# SCH_Uno-Balancer.net
KiCad netlist of a schematic drawn in Altium Designer
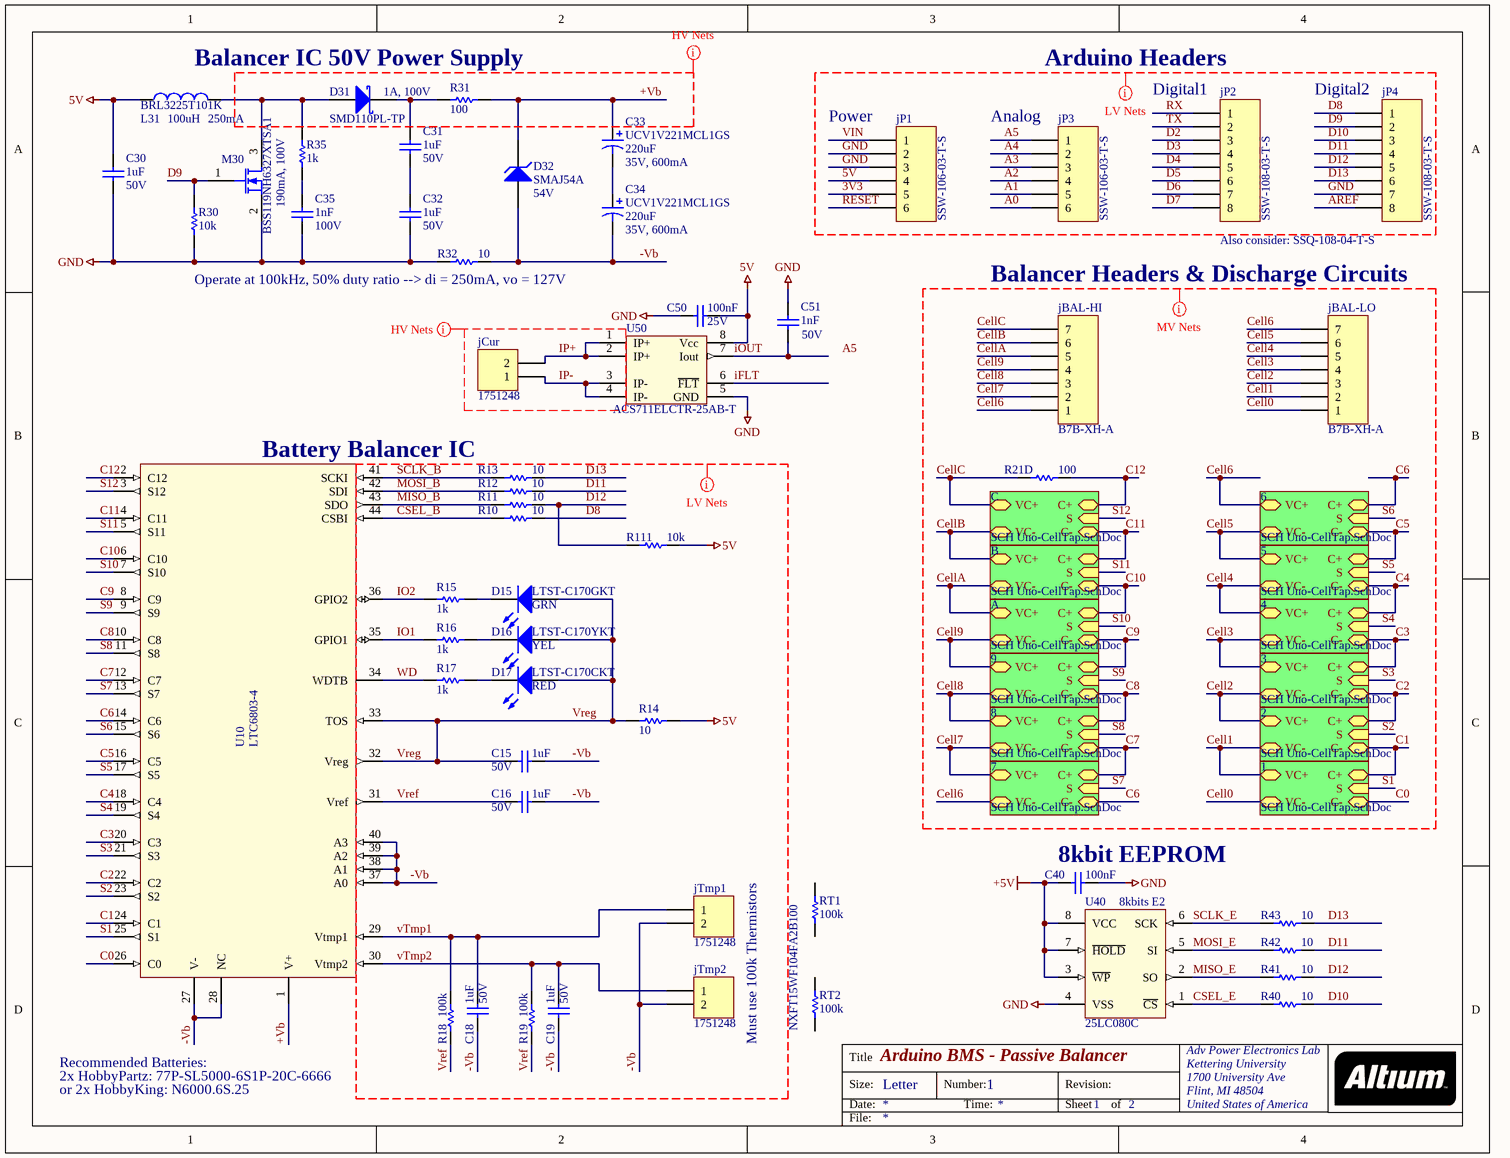
[diagram p0: SCH Uno-Balancer.SchDoc]

(export (version "E")
  (design (tool "Eeschema 10.0.6"))
  (components
    (comp (ref "C15")
      (value "1uF")
      (footprint "CAPC2012N")
      (description "Capacitor")
      (fields (field (name "RATED") "50V") (field (name "Comment") "CL21F105ZBFNNNE"))
      (libsource (lib "Miscellaneous Devices") (part "Cap"))
    )
    (comp (ref "C16")
      (value "1uF")
      (footprint "CAPC2012N")
      (description "Capacitor")
      (fields (field (name "RATED") "50V") (field (name "Comment") "CL21F105ZBFNNNE"))
      (libsource (lib "Miscellaneous Devices") (part "Cap"))
    )
    (comp (ref "C18")
      (value "1uF")
      (footprint "CAPC2012N")
      (description "Capacitor")
      (fields (field (name "RATED") "50V") (field (name "Comment") "CL21F105ZBFNNNE"))
      (libsource (lib "Miscellaneous Devices") (part "Cap"))
    )
    (comp (ref "C19")
      (value "1uF")
      (footprint "CAPC2012N")
      (description "Capacitor")
      (fields (field (name "RATED") "50V") (field (name "Comment") "CL21F105ZBFNNNE"))
      (libsource (lib "Miscellaneous Devices") (part "Cap"))
    )
    (comp (ref "C30")
      (value "1uF")
      (footprint "CAPC2012N")
      (description "Capacitor")
      (fields (field (name "RATED") "50V") (field (name "Comment") "CL21F105ZBFNNNE"))
      (libsource (lib "Miscellaneous Devices") (part "Cap"))
    )
    (comp (ref "C31")
      (value "1uF")
      (footprint "CAPC2012N")
      (description "Capacitor")
      (fields (field (name "RATED") "50V") (field (name "Comment") "CL21F105ZBFNNNE"))
      (libsource (lib "Miscellaneous Devices") (part "Cap"))
    )
    (comp (ref "C32")
      (value "1uF")
      (footprint "CAPC2012N")
      (description "Capacitor")
      (fields (field (name "RATED") "50V") (field (name "Comment") "CL21F105ZBFNNNE"))
      (libsource (lib "Miscellaneous Devices") (part "Cap"))
    )
    (comp (ref "C33")
      (value "UCV1V221MCL1GS")
      (footprint "CAP SMT 6.3x8mm")
      (description "Aluminum Electrolytic Capacitor")
      (fields (field (name "ALTIUM_VALUE") "220uF") (field (name "RATED") "35V, 600mA"))
      (libsource (lib "Miscellaneous Devices") (part "Cap Pol1"))
    )
    (comp (ref "C34")
      (value "UCV1V221MCL1GS")
      (footprint "CAP SMT 6.3x8mm")
      (description "Aluminum Electrolytic Capacitor")
      (fields (field (name "ALTIUM_VALUE") "220uF") (field (name "RATED") "35V, 600mA"))
      (libsource (lib "Miscellaneous Devices") (part "Cap Pol1"))
    )
    (comp (ref "C35")
      (value "1nF")
      (footprint "CAPC2012N")
      (description "Capacitor")
      (fields (field (name "RATED") "100V") (field (name "Comment") "C0805C102K1RACTU"))
      (libsource (lib "Miscellaneous Devices") (part "Cap"))
    )
    (comp (ref "C40")
      (value "100nF")
      (footprint "CAPC2012N")
      (description "Capacitor")
      (fields (field (name "Comment") "C0805C104Z5VACTU"))
      (libsource (lib "Miscellaneous Devices") (part "Cap"))
    )
    (comp (ref "C50")
      (value "100nF")
      (footprint "CAPC2012N")
      (description "Capacitor")
      (fields (field (name "RATED") "25V") (field (name "Comment") "C0805C104M3RACTU"))
      (libsource (lib "Miscellaneous Devices") (part "Cap"))
    )
    (comp (ref "C51")
      (value "1nF")
      (footprint "CAPC2012N")
      (description "Capacitor")
      (fields (field (name "RATED") "50V") (field (name "Comment") "C0805C102K5RACTU"))
      (libsource (lib "Miscellaneous Devices") (part "Cap"))
    )
    (comp (ref "D15")
      (value "LTST-C170GKT")
      (footprint "DIO2012N-G")
      (description "SMT Green Si LED")
      (fields (field (name "ALTIUM_VALUE") "GRN"))
      (libsource (lib "LIB SCH ArduinoBMS") (part "LTST-C170GKT"))
    )
    (comp (ref "D16")
      (value "LTST-C170YKT")
      (footprint "DIO2012N-Y")
      (description "SMT Yellow Si LED")
      (fields (field (name "ALTIUM_VALUE") "YEL"))
      (libsource (lib "LIB SCH ArduinoBMS") (part "LTST-C170YKT"))
    )
    (comp (ref "D17")
      (value "LTST-C170CKT")
      (footprint "DIO2012N-R")
      (description "SMT Red Si LED")
      (fields (field (name "ALTIUM_VALUE") "RED"))
      (libsource (lib "LIB SCH ArduinoBMS") (part "LTST-C170CKT"))
    )
    (comp (ref "D31")
      (value "SMD110PL-TP")
      (footprint "SOD123")
      (description "Silicon Schottky Diode, 1A, 100V")
      (fields (field (name "RATED") "1A, 100V"))
      (libsource (lib "LIB SCH ArduinoBMS") (part "SMD110PL-TP"))
    )
    (comp (ref "D32")
      (value "SMAJ54A")
      (footprint "DO214-SMA")
      (description "Zener Diode")
      (fields (field (name "ALTIUM_VALUE") "54V"))
      (libsource (lib "Miscellaneous Devices") (part "D Zener"))
    )
    (comp (ref "jBAL-HI")
      (value "B7B-XH-A")
      (footprint "JST-XH-B7")
      (description "JST Battery Balance Port Header, 7-Pin")
      (libsource (lib "LIB SCH ArduinoBMS") (part "JST B7B-XH-A"))
    )
    (comp (ref "jBAL-LO")
      (value "B7B-XH-A")
      (footprint "JST-XH-B7")
      (description "JST Battery Balance Port Header, 7-Pin")
      (libsource (lib "LIB SCH ArduinoBMS") (part "JST B7B-XH-A"))
    )
    (comp (ref "jCur")
      (value "1751248")
      (footprint "TERM2x3.5mm")
      (description "Header Conn Term Block, 2-Pin, 3.5mm Pitch")
      (libsource (lib "Miscellaneous Connectors") (part "Header 2"))
    )
    (comp (ref "jP1")
      (value "SSW-106-03-T-S")
      (footprint "HDR1X6")
      (description "Header, 6-Pin")
      (libsource (lib "Miscellaneous Connectors") (part "Header 6"))
    )
    (comp (ref "jP2")
      (value "SSW-108-03-T-S")
      (footprint "HDR1X8")
      (description "Header, 8-Pin")
      (libsource (lib "Miscellaneous Connectors") (part "Header 8"))
    )
    (comp (ref "jP3")
      (value "SSW-106-03-T-S")
      (footprint "HDR1X6")
      (description "Header, 6-Pin")
      (libsource (lib "Miscellaneous Connectors") (part "Header 6"))
    )
    (comp (ref "jP4")
      (value "SSW-108-03-T-S")
      (footprint "HDR1X8")
      (description "Header, 8-Pin")
      (libsource (lib "Miscellaneous Connectors") (part "Header 8"))
    )
    (comp (ref "jTmp1")
      (value "1751248")
      (footprint "TERM2x3.5mm")
      (description "Header Conn Term Block, 2-Pin, 3.5mm Pitch")
      (libsource (lib "") (part "Header 2_1"))
    )
    (comp (ref "jTmp2")
      (value "1751248")
      (footprint "TERM2x3.5mm")
      (description "Header Conn Term Block, 2-Pin, 3.5mm Pitch")
      (libsource (lib "") (part "Header 2_1"))
    )
    (comp (ref "L31")
      (value "BRL3225T101K")
      (footprint "INDC3225N")
      (description "Ferrite Bead Inductor")
      (fields (field (name "ALTIUM_VALUE") "100uH") (field (name "RATED") "250mA"))
      (libsource (lib "MagnaPFC") (part "BLM21P221SN"))
    )
    (comp (ref "M30")
      (value "BSS119NH6327XTSA1")
      (footprint "SOT23-3N")
      (description "Low-Power N-Channel MOSFET, 100V 170mA")
      (fields (field (name "RATED") "190mA, 100V"))
      (libsource (lib "LIB SCH ArduinoBMS") (part "BSS123"))
    )
    (comp (ref "R10")
      (value "10")
      (footprint "RESC2012N")
      (description "Resistor")
      (fields (field (name "Comment") "ERJ-6ENF10R0V"))
      (libsource (lib "Miscellaneous Devices") (part "Res1"))
    )
    (comp (ref "R11")
      (value "10")
      (footprint "RESC2012N")
      (description "Resistor")
      (fields (field (name "Comment") "ERJ-6ENF10R0V"))
      (libsource (lib "Miscellaneous Devices") (part "Res1"))
    )
    (comp (ref "R12")
      (value "10")
      (footprint "RESC2012N")
      (description "Resistor")
      (fields (field (name "Comment") "ERJ-6ENF10R0V"))
      (libsource (lib "Miscellaneous Devices") (part "Res1"))
    )
    (comp (ref "R13")
      (value "10")
      (footprint "RESC2012N")
      (description "Resistor")
      (fields (field (name "Comment") "ERJ-6ENF10R0V"))
      (libsource (lib "Miscellaneous Devices") (part "Res1"))
    )
    (comp (ref "R14")
      (value "10")
      (footprint "RESC2012N")
      (description "Resistor")
      (fields (field (name "Comment") "ERJ-6ENF10R0V"))
      (libsource (lib "Miscellaneous Devices") (part "Res1"))
    )
    (comp (ref "R15")
      (value "1k")
      (footprint "RESC2012N")
      (description "Resistor")
      (fields (field (name "Comment") "ERJ-6ENF1001V"))
      (libsource (lib "Miscellaneous Devices") (part "Res1"))
    )
    (comp (ref "R16")
      (value "1k")
      (footprint "RESC2012N")
      (description "Resistor")
      (fields (field (name "Comment") "ERJ-6ENF1001V"))
      (libsource (lib "Miscellaneous Devices") (part "Res1"))
    )
    (comp (ref "R17")
      (value "1k")
      (footprint "RESC2012N")
      (description "Resistor")
      (fields (field (name "Comment") "ERJ-6ENF1001V"))
      (libsource (lib "Miscellaneous Devices") (part "Res1"))
    )
    (comp (ref "R18")
      (value "100k")
      (footprint "RESC2012N")
      (description "Resistor")
      (fields (field (name "Comment") "ERJ-6ENF1003V"))
      (libsource (lib "Miscellaneous Devices") (part "Res1"))
    )
    (comp (ref "R19")
      (value "100k")
      (footprint "RESC2012N")
      (description "Resistor")
      (fields (field (name "Comment") "ERJ-6ENF1003V"))
      (libsource (lib "Miscellaneous Devices") (part "Res1"))
    )
    (comp (ref "R21D")
      (value "100")
      (footprint "RESC2012N")
      (description "Resistor")
      (fields (field (name "Comment") "ERJ-6ENF1000V"))
      (libsource (lib "Miscellaneous Devices") (part "Res1"))
    )
    (comp (ref "R30")
      (value "10k")
      (footprint "RESC2012N")
      (description "Resistor")
      (fields (field (name "Comment") "ERJ-6ENF1002V"))
      (libsource (lib "Miscellaneous Devices") (part "Res1"))
    )
    (comp (ref "R31")
      (value "100")
      (footprint "RESC2012N")
      (description "Resistor")
      (fields (field (name "Comment") "ERJ-6ENF1000V"))
      (libsource (lib "Miscellaneous Devices") (part "Res1"))
    )
    (comp (ref "R32")
      (value "10")
      (footprint "RESC2012N")
      (description "Resistor")
      (fields (field (name "Comment") "ERJ-6ENF10R0V"))
      (libsource (lib "Miscellaneous Devices") (part "Res1"))
    )
    (comp (ref "R35")
      (value "1k")
      (footprint "RESC2012N")
      (description "Resistor")
      (fields (field (name "Comment") "ERJ-6ENF1001V"))
      (libsource (lib "Miscellaneous Devices") (part "Res1"))
    )
    (comp (ref "R40")
      (value "10")
      (footprint "RESC2012N")
      (description "Resistor")
      (fields (field (name "Comment") "ERJ-6ENF10R0V"))
      (libsource (lib "Miscellaneous Devices") (part "Res1"))
    )
    (comp (ref "R41")
      (value "10")
      (footprint "RESC2012N")
      (description "Resistor")
      (fields (field (name "Comment") "ERJ-6ENF10R0V"))
      (libsource (lib "Miscellaneous Devices") (part "Res1"))
    )
    (comp (ref "R42")
      (value "10")
      (footprint "RESC2012N")
      (description "Resistor")
      (fields (field (name "Comment") "ERJ-6ENF10R0V"))
      (libsource (lib "Miscellaneous Devices") (part "Res1"))
    )
    (comp (ref "R43")
      (value "10")
      (footprint "RESC2012N")
      (description "Resistor")
      (fields (field (name "Comment") "ERJ-6ENF10R0V"))
      (libsource (lib "Miscellaneous Devices") (part "Res1"))
    )
    (comp (ref "R111")
      (value "10k")
      (footprint "RESC2012N")
      (description "Resistor")
      (fields (field (name "Comment") "ERJ-6ENF1002V"))
      (libsource (lib "Miscellaneous Devices") (part "Res1"))
    )
    (comp (ref "RT1")
      (value "100k")
      (description "NTC Thermistor Resistor")
      (fields (field (name "Comment") "NXFT15WF104FA2B100"))
      (libsource (lib "Miscellaneous Devices") (part "Res1"))
    )
    (comp (ref "RT2")
      (value "100k")
      (description "NTC Thermistor Resistor")
      (fields (field (name "Comment") "NXFT15WF104FA2B100"))
      (libsource (lib "Miscellaneous Devices") (part "Res1"))
    )
    (comp (ref "U10")
      (value "LTC6803-4")
      (footprint "SSOP44")
      (description "Multicell Battery Stack Monitor")
      (libsource (lib "LIB SCH Three Phase") (part "LTC6803-4"))
    )
    (comp (ref "U40")
      (value "25LC080C")
      (footprint "SOIC-8-150")
      (description "EEPROM 8kbit SPI Serial Interface")
      (fields (field (name "ALTIUM_VALUE") "8kbits E2"))
      (libsource (lib "LIB SCH NBT Inverter") (part "25LC080C"))
    )
    (comp (ref "U50")
      (value "ACS711ELCTR-25AB-T")
      (footprint "SOIC-8-150")
      (description "Internal Hall-Effect Current Transducer")
      (libsource (lib "LIB SCH NanoInv") (part "ACS711"))
    )
  )
  (nets
    (net (code "1") (name "+5V") (class "Default")
      (node (ref "C40") (pin "2") (pinfunction "2_2") (pintype "passive"))
      (node (ref "U40") (pin "3") (pinfunction "~{WP}_3") (pintype "input"))
      (node (ref "U40") (pin "7") (pinfunction "~{HOLD}_7") (pintype "input"))
      (node (ref "U40") (pin "8") (pinfunction "VCC_8") (pintype "power_in"))
    )
    (net (code "2") (name "/+Vb") (class "Default")
      (node (ref "C33") (pin "1") (pinfunction "1_1") (pintype "passive"))
      (node (ref "D32") (pin "2") (pinfunction "K_2") (pintype "passive"))
      (node (ref "R31") (pin "2") (pinfunction "2_2") (pintype "passive"))
      (node (ref "U10") (pin "1") (pinfunction "V+_1") (pintype "power_in"))
    )
    (net (code "3") (name "/-Vb") (class "Default")
      (node (ref "C15") (pin "1") (pinfunction "1_1") (pintype "passive"))
      (node (ref "C16") (pin "1") (pinfunction "1_1") (pintype "passive"))
      (node (ref "C18") (pin "1") (pinfunction "1_1") (pintype "passive"))
      (node (ref "C19") (pin "1") (pinfunction "1_1") (pintype "passive"))
      (node (ref "C34") (pin "2") (pinfunction "2_2") (pintype "passive"))
      (node (ref "D32") (pin "1") (pinfunction "A_1") (pintype "passive"))
      (node (ref "R32") (pin "2") (pinfunction "2_2") (pintype "passive"))
      (node (ref "U10") (pin "27") (pinfunction "V-_27") (pintype "power_in"))
      (node (ref "U10") (pin "28") (pinfunction "NC_28") (pintype "passive"))
      (node (ref "U10") (pin "37") (pinfunction "A0_37") (pintype "input"))
      (node (ref "U10") (pin "38") (pinfunction "A1_38") (pintype "input"))
      (node (ref "U10") (pin "39") (pinfunction "A2_39") (pintype "input"))
      (node (ref "U10") (pin "40") (pinfunction "A3_40") (pintype "input"))
      (node (ref "jTmp1") (pin "2") (pinfunction "2_2") (pintype "passive"))
      (node (ref "jTmp2") (pin "2") (pinfunction "2_2") (pintype "passive"))
    )
    (net (code "4") (name "/3V3") (class "Default")
      (node (ref "jP1") (pin "5") (pinfunction "5_5") (pintype "passive"))
    )
    (net (code "5") (name "/A0") (class "Default")
      (node (ref "jP3") (pin "6") (pinfunction "6_6") (pintype "passive"))
    )
    (net (code "6") (name "/A1") (class "Default")
      (node (ref "jP3") (pin "5") (pinfunction "5_5") (pintype "passive"))
    )
    (net (code "7") (name "/A2") (class "Default")
      (node (ref "jP3") (pin "4") (pinfunction "4_4") (pintype "passive"))
    )
    (net (code "8") (name "/A3") (class "Default")
      (node (ref "jP3") (pin "3") (pinfunction "3_3") (pintype "passive"))
    )
    (net (code "9") (name "/A4") (class "Default")
      (node (ref "jP3") (pin "2") (pinfunction "2_2") (pintype "passive"))
    )
    (net (code "10") (name "/A5") (class "Default")
      (node (ref "jP3") (pin "1") (pinfunction "1_1") (pintype "passive"))
    )
    (net (code "11") (name "/AREF") (class "Default")
      (node (ref "jP4") (pin "8") (pinfunction "8_8") (pintype "passive"))
    )
    (net (code "12") (name "/C0") (class "Default")
      (node (ref "U10") (pin "26") (pinfunction "C0_26") (pintype "input"))
    )
    (net (code "13") (name "/C1") (class "Default")
      (node (ref "U10") (pin "24") (pinfunction "C1_24") (pintype "input"))
    )
    (net (code "14") (name "/C2") (class "Default")
      (node (ref "U10") (pin "22") (pinfunction "C2_22") (pintype "input"))
    )
    (net (code "15") (name "/C3") (class "Default")
      (node (ref "U10") (pin "20") (pinfunction "C3_20") (pintype "input"))
    )
    (net (code "16") (name "/C4") (class "Default")
      (node (ref "U10") (pin "18") (pinfunction "C4_18") (pintype "input"))
    )
    (net (code "17") (name "/C5") (class "Default")
      (node (ref "U10") (pin "16") (pinfunction "C5_16") (pintype "input"))
    )
    (net (code "18") (name "/C6") (class "Default")
      (node (ref "U10") (pin "14") (pinfunction "C6_14") (pintype "input"))
    )
    (net (code "19") (name "/C7") (class "Default")
      (node (ref "U10") (pin "12") (pinfunction "C7_12") (pintype "input"))
    )
    (net (code "20") (name "/C8") (class "Default")
      (node (ref "U10") (pin "10") (pinfunction "C8_10") (pintype "input"))
    )
    (net (code "21") (name "/C9") (class "Default")
      (node (ref "U10") (pin "8") (pinfunction "C9_8") (pintype "input"))
    )
    (net (code "22") (name "/C10") (class "Default")
      (node (ref "U10") (pin "6") (pinfunction "C10_6") (pintype "input"))
    )
    (net (code "23") (name "/C11") (class "Default")
      (node (ref "U10") (pin "4") (pinfunction "C11_4") (pintype "input"))
    )
    (net (code "24") (name "/C12") (class "Default")
      (node (ref "R21D") (pin "2") (pinfunction "2_2") (pintype "passive"))
      (node (ref "U10") (pin "2") (pinfunction "C12_2") (pintype "input"))
    )
    (net (code "25") (name "/CSEL_B") (class "Default")
      (node (ref "R10") (pin "1") (pinfunction "1_1") (pintype "passive"))
      (node (ref "U10") (pin "44") (pinfunction "CSBI_44") (pintype "input"))
    )
    (net (code "26") (name "/CSEL_E") (class "Default")
      (node (ref "R40") (pin "1") (pinfunction "1_1") (pintype "passive"))
      (node (ref "U40") (pin "1") (pinfunction "~{CS}_1") (pintype "input"))
    )
    (net (code "27") (name "/Cell0") (class "Default")
      (node (ref "jBAL-LO") (pin "1") (pinfunction "1_1") (pintype "passive"))
    )
    (net (code "28") (name "/Cell1") (class "Default")
      (node (ref "jBAL-LO") (pin "2") (pinfunction "2_2") (pintype "passive"))
    )
    (net (code "29") (name "/Cell2") (class "Default")
      (node (ref "jBAL-LO") (pin "3") (pinfunction "3_3") (pintype "passive"))
    )
    (net (code "30") (name "/Cell3") (class "Default")
      (node (ref "jBAL-LO") (pin "4") (pinfunction "4_4") (pintype "passive"))
    )
    (net (code "31") (name "/Cell4") (class "Default")
      (node (ref "jBAL-LO") (pin "5") (pinfunction "5_5") (pintype "passive"))
    )
    (net (code "32") (name "/Cell5") (class "Default")
      (node (ref "jBAL-LO") (pin "6") (pinfunction "6_6") (pintype "passive"))
    )
    (net (code "33") (name "/Cell6") (class "Default")
      (node (ref "jBAL-HI") (pin "1") (pinfunction "1_1") (pintype "passive"))
      (node (ref "jBAL-LO") (pin "7") (pinfunction "7_7") (pintype "passive"))
    )
    (net (code "34") (name "/Cell7") (class "Default")
      (node (ref "jBAL-HI") (pin "2") (pinfunction "2_2") (pintype "passive"))
    )
    (net (code "35") (name "/Cell8") (class "Default")
      (node (ref "jBAL-HI") (pin "3") (pinfunction "3_3") (pintype "passive"))
    )
    (net (code "36") (name "/Cell9") (class "Default")
      (node (ref "jBAL-HI") (pin "4") (pinfunction "4_4") (pintype "passive"))
    )
    (net (code "37") (name "/CellA") (class "Default")
      (node (ref "jBAL-HI") (pin "5") (pinfunction "5_5") (pintype "passive"))
    )
    (net (code "38") (name "/CellB") (class "Default")
      (node (ref "jBAL-HI") (pin "6") (pinfunction "6_6") (pintype "passive"))
    )
    (net (code "39") (name "/CellC") (class "Default")
      (node (ref "R21D") (pin "1") (pinfunction "1_1") (pintype "passive"))
      (node (ref "jBAL-HI") (pin "7") (pinfunction "7_7") (pintype "passive"))
    )
    (net (code "40") (name "/D2") (class "Default")
      (node (ref "jP2") (pin "3") (pinfunction "3_3") (pintype "passive"))
    )
    (net (code "41") (name "/D3") (class "Default")
      (node (ref "jP2") (pin "4") (pinfunction "4_4") (pintype "passive"))
    )
    (net (code "42") (name "/D4") (class "Default")
      (node (ref "jP2") (pin "5") (pinfunction "5_5") (pintype "passive"))
    )
    (net (code "43") (name "/D5") (class "Default")
      (node (ref "jP2") (pin "6") (pinfunction "6_6") (pintype "passive"))
    )
    (net (code "44") (name "/D6") (class "Default")
      (node (ref "jP2") (pin "7") (pinfunction "7_7") (pintype "passive"))
    )
    (net (code "45") (name "/D7") (class "Default")
      (node (ref "jP2") (pin "8") (pinfunction "8_8") (pintype "passive"))
    )
    (net (code "46") (name "/D8") (class "Default")
      (node (ref "R10") (pin "2") (pinfunction "2_2") (pintype "passive"))
      (node (ref "jP4") (pin "1") (pinfunction "1_1") (pintype "passive"))
    )
    (net (code "47") (name "/D9") (class "Default")
      (node (ref "M30") (pin "1") (pinfunction "G_1") (pintype "passive"))
      (node (ref "R30") (pin "1") (pinfunction "1_1") (pintype "passive"))
      (node (ref "jP4") (pin "2") (pinfunction "2_2") (pintype "passive"))
    )
    (net (code "48") (name "/D10") (class "Default")
      (node (ref "R40") (pin "2") (pinfunction "2_2") (pintype "passive"))
      (node (ref "jP4") (pin "3") (pinfunction "3_3") (pintype "passive"))
    )
    (net (code "49") (name "/D11") (class "Default")
      (node (ref "R12") (pin "2") (pinfunction "2_2") (pintype "passive"))
      (node (ref "R42") (pin "2") (pinfunction "2_2") (pintype "passive"))
      (node (ref "jP4") (pin "4") (pinfunction "4_4") (pintype "passive"))
    )
    (net (code "50") (name "/D12") (class "Default")
      (node (ref "R11") (pin "2") (pinfunction "2_2") (pintype "passive"))
      (node (ref "R111") (pin "1") (pinfunction "1_1") (pintype "passive"))
      (node (ref "R41") (pin "2") (pinfunction "2_2") (pintype "passive"))
      (node (ref "jP4") (pin "5") (pinfunction "5_5") (pintype "passive"))
    )
    (net (code "51") (name "/D13") (class "Default")
      (node (ref "R13") (pin "2") (pinfunction "2_2") (pintype "passive"))
      (node (ref "R43") (pin "2") (pinfunction "2_2") (pintype "passive"))
      (node (ref "jP4") (pin "6") (pinfunction "6_6") (pintype "passive"))
    )
    (net (code "52") (name "/IO1") (class "Default")
      (node (ref "R16") (pin "2") (pinfunction "2_2") (pintype "passive"))
      (node (ref "U10") (pin "35") (pinfunction "GPIO1_35") (pintype "bidirectional"))
    )
    (net (code "53") (name "/IO2") (class "Default")
      (node (ref "R15") (pin "2") (pinfunction "2_2") (pintype "passive"))
      (node (ref "U10") (pin "36") (pinfunction "GPIO2_36") (pintype "bidirectional"))
    )
    (net (code "54") (name "/IP+") (class "Default")
      (node (ref "U50") (pin "1") (pinfunction "IP+_1") (pintype "passive"))
      (node (ref "U50") (pin "2") (pinfunction "IP+_2") (pintype "passive"))
      (node (ref "jCur") (pin "2") (pinfunction "2_2") (pintype "passive"))
    )
    (net (code "55") (name "/IP-") (class "Default")
      (node (ref "U50") (pin "3") (pinfunction "IP-_3") (pintype "passive"))
      (node (ref "U50") (pin "4") (pinfunction "IP-_4") (pintype "passive"))
      (node (ref "jCur") (pin "1") (pinfunction "1_1") (pintype "passive"))
    )
    (net (code "56") (name "/MISO_B") (class "Default")
      (node (ref "R11") (pin "1") (pinfunction "1_1") (pintype "passive"))
      (node (ref "U10") (pin "43") (pinfunction "SDO_43") (pintype "output"))
    )
    (net (code "57") (name "/MISO_E") (class "Default")
      (node (ref "R41") (pin "1") (pinfunction "1_1") (pintype "passive"))
      (node (ref "U40") (pin "2") (pinfunction "SO_2") (pintype "output"))
    )
    (net (code "58") (name "/MOSI_B") (class "Default")
      (node (ref "R12") (pin "1") (pinfunction "1_1") (pintype "passive"))
      (node (ref "U10") (pin "42") (pinfunction "SDI_42") (pintype "input"))
    )
    (net (code "59") (name "/MOSI_E") (class "Default")
      (node (ref "R42") (pin "1") (pinfunction "1_1") (pintype "passive"))
      (node (ref "U40") (pin "5") (pinfunction "SI_5") (pintype "input"))
    )
    (net (code "60") (name "/RESET") (class "Default")
      (node (ref "jP1") (pin "6") (pinfunction "6_6") (pintype "passive"))
    )
    (net (code "61") (name "/RX") (class "Default")
      (node (ref "jP2") (pin "1") (pinfunction "1_1") (pintype "passive"))
    )
    (net (code "62") (name "/S1") (class "Default")
      (node (ref "U10") (pin "25") (pinfunction "S1_25") (pintype "output"))
    )
    (net (code "63") (name "/S2") (class "Default")
      (node (ref "U10") (pin "23") (pinfunction "S2_23") (pintype "output"))
    )
    (net (code "64") (name "/S3") (class "Default")
      (node (ref "U10") (pin "21") (pinfunction "S3_21") (pintype "output"))
    )
    (net (code "65") (name "/S4") (class "Default")
      (node (ref "U10") (pin "19") (pinfunction "S4_19") (pintype "output"))
    )
    (net (code "66") (name "/S5") (class "Default")
      (node (ref "U10") (pin "17") (pinfunction "S5_17") (pintype "output"))
    )
    (net (code "67") (name "/S6") (class "Default")
      (node (ref "U10") (pin "15") (pinfunction "S6_15") (pintype "output"))
    )
    (net (code "68") (name "/S7") (class "Default")
      (node (ref "U10") (pin "13") (pinfunction "S7_13") (pintype "output"))
    )
    (net (code "69") (name "/S8") (class "Default")
      (node (ref "U10") (pin "11") (pinfunction "S8_11") (pintype "output"))
    )
    (net (code "70") (name "/S9") (class "Default")
      (node (ref "U10") (pin "9") (pinfunction "S9_9") (pintype "output"))
    )
    (net (code "71") (name "/S10") (class "Default")
      (node (ref "U10") (pin "7") (pinfunction "S10_7") (pintype "output"))
    )
    (net (code "72") (name "/S11") (class "Default")
      (node (ref "U10") (pin "5") (pinfunction "S11_5") (pintype "output"))
    )
    (net (code "73") (name "/S12") (class "Default")
      (node (ref "U10") (pin "3") (pinfunction "S12_3") (pintype "output"))
    )
    (net (code "74") (name "/SCLK_B") (class "Default")
      (node (ref "R13") (pin "1") (pinfunction "1_1") (pintype "passive"))
      (node (ref "U10") (pin "41") (pinfunction "SCKI_41") (pintype "input"))
    )
    (net (code "75") (name "/SCLK_E") (class "Default")
      (node (ref "R43") (pin "1") (pinfunction "1_1") (pintype "passive"))
      (node (ref "U40") (pin "6") (pinfunction "SCK_6") (pintype "input"))
    )
    (net (code "76") (name "/TX") (class "Default")
      (node (ref "jP2") (pin "2") (pinfunction "2_2") (pintype "passive"))
    )
    (net (code "77") (name "/VIN") (class "Default")
      (node (ref "jP1") (pin "1") (pinfunction "1_1") (pintype "passive"))
    )
    (net (code "78") (name "/Vref") (class "Default")
      (node (ref "C16") (pin "2") (pinfunction "2_2") (pintype "passive"))
      (node (ref "R18") (pin "1") (pinfunction "1_1") (pintype "passive"))
      (node (ref "R19") (pin "1") (pinfunction "1_1") (pintype "passive"))
      (node (ref "U10") (pin "31") (pinfunction "Vref_31") (pintype "output"))
    )
    (net (code "79") (name "/Vreg") (class "Default")
      (node (ref "C15") (pin "2") (pinfunction "2_2") (pintype "passive"))
      (node (ref "D15") (pin "1") (pinfunction "A_1") (pintype "passive"))
      (node (ref "D16") (pin "1") (pinfunction "A_1") (pintype "passive"))
      (node (ref "D17") (pin "1") (pinfunction "A_1") (pintype "passive"))
      (node (ref "R14") (pin "1") (pinfunction "1_1") (pintype "passive"))
      (node (ref "U10") (pin "32") (pinfunction "Vreg_32") (pintype "output"))
      (node (ref "U10") (pin "33") (pinfunction "TOS_33") (pintype "input"))
    )
    (net (code "80") (name "/WD") (class "Default")
      (node (ref "R17") (pin "2") (pinfunction "2_2") (pintype "passive"))
      (node (ref "U10") (pin "34") (pinfunction "WDTB_34") (pintype "open_collector"))
    )
    (net (code "81") (name "/iFLT") (class "Default")
      (node (ref "U50") (pin "6") (pinfunction "~{FLT}_6") (pintype "open_collector"))
    )
    (net (code "82") (name "/iOUT") (class "Default")
      (node (ref "C51") (pin "2") (pinfunction "2_2") (pintype "passive"))
      (node (ref "U50") (pin "7") (pinfunction "Iout_7") (pintype "output"))
    )
    (net (code "83") (name "/vTmp1") (class "Default")
      (node (ref "C18") (pin "2") (pinfunction "2_2") (pintype "passive"))
      (node (ref "R18") (pin "2") (pinfunction "2_2") (pintype "passive"))
      (node (ref "U10") (pin "29") (pinfunction "Vtmp1_29") (pintype "input"))
      (node (ref "jTmp1") (pin "1") (pinfunction "1_1") (pintype "passive"))
    )
    (net (code "84") (name "/vTmp2") (class "Default")
      (node (ref "C19") (pin "2") (pinfunction "2_2") (pintype "passive"))
      (node (ref "R19") (pin "2") (pinfunction "2_2") (pintype "passive"))
      (node (ref "U10") (pin "30") (pinfunction "Vtmp2_30") (pintype "input"))
      (node (ref "jTmp2") (pin "1") (pinfunction "1_1") (pintype "passive"))
    )
    (net (code "85") (name "5V") (class "Default")
      (node (ref "C30") (pin "1") (pinfunction "1_1") (pintype "passive"))
      (node (ref "C50") (pin "1") (pinfunction "1_1") (pintype "passive"))
      (node (ref "L31") (pin "1") (pinfunction "1_1") (pintype "passive"))
      (node (ref "R111") (pin "2") (pinfunction "2_2") (pintype "passive"))
      (node (ref "R14") (pin "2") (pinfunction "2_2") (pintype "passive"))
      (node (ref "U50") (pin "8") (pinfunction "Vcc_8") (pintype "power_in"))
      (node (ref "jP1") (pin "4") (pinfunction "4_4") (pintype "passive"))
    )
    (net (code "86") (name "GND") (class "Default")
      (node (ref "C30") (pin "2") (pinfunction "2_2") (pintype "passive"))
      (node (ref "C32") (pin "2") (pinfunction "2_2") (pintype "passive"))
      (node (ref "C35") (pin "2") (pinfunction "2_2") (pintype "passive"))
      (node (ref "C40") (pin "1") (pinfunction "1_1") (pintype "passive"))
      (node (ref "C50") (pin "2") (pinfunction "2_2") (pintype "passive"))
      (node (ref "C51") (pin "1") (pinfunction "1_1") (pintype "passive"))
      (node (ref "M30") (pin "2") (pinfunction "S_2") (pintype "passive"))
      (node (ref "R30") (pin "2") (pinfunction "2_2") (pintype "passive"))
      (node (ref "R32") (pin "1") (pinfunction "1_1") (pintype "passive"))
      (node (ref "U40") (pin "4") (pinfunction "VSS_4") (pintype "power_in"))
      (node (ref "U50") (pin "5") (pinfunction "GND_5") (pintype "power_in"))
      (node (ref "jP1") (pin "2") (pinfunction "2_2") (pintype "passive"))
      (node (ref "jP1") (pin "3") (pinfunction "3_3") (pintype "passive"))
      (node (ref "jP4") (pin "7") (pinfunction "7_7") (pintype "passive"))
    )
    (net (code "87") (name "Net-(C31-Pad2)") (class "Default")
      (node (ref "C31") (pin "2") (pinfunction "2_2") (pintype "passive"))
      (node (ref "C32") (pin "1") (pinfunction "1_1") (pintype "passive"))
    )
    (net (code "88") (name "Net-(C33-Pad2)") (class "Default")
      (node (ref "C33") (pin "2") (pinfunction "2_2") (pintype "passive"))
      (node (ref "C34") (pin "1") (pinfunction "1_1") (pintype "passive"))
    )
    (net (code "89") (name "Net-(C35-Pad1)") (class "Default")
      (node (ref "C35") (pin "1") (pinfunction "1_1") (pintype "passive"))
      (node (ref "R35") (pin "2") (pinfunction "2_2") (pintype "passive"))
    )
    (net (code "90") (name "Net-(D15-K)") (class "Default")
      (node (ref "D15") (pin "2") (pinfunction "K_2") (pintype "passive"))
      (node (ref "R15") (pin "1") (pinfunction "1_1") (pintype "passive"))
    )
    (net (code "91") (name "Net-(D16-K)") (class "Default")
      (node (ref "D16") (pin "2") (pinfunction "K_2") (pintype "passive"))
      (node (ref "R16") (pin "1") (pinfunction "1_1") (pintype "passive"))
    )
    (net (code "92") (name "Net-(D17-K)") (class "Default")
      (node (ref "D17") (pin "2") (pinfunction "K_2") (pintype "passive"))
      (node (ref "R17") (pin "1") (pinfunction "1_1") (pintype "passive"))
    )
    (net (code "93") (name "Net-(D31-A)") (class "Default")
      (node (ref "D31") (pin "1") (pinfunction "A_1") (pintype "passive"))
      (node (ref "L31") (pin "2") (pinfunction "2_2") (pintype "passive"))
      (node (ref "M30") (pin "3") (pinfunction "D_3") (pintype "passive"))
      (node (ref "R35") (pin "1") (pinfunction "1_1") (pintype "passive"))
    )
    (net (code "94") (name "Net-(D31-K)") (class "Default")
      (node (ref "C31") (pin "1") (pinfunction "1_1") (pintype "passive"))
      (node (ref "D31") (pin "2") (pinfunction "K_2") (pintype "passive"))
      (node (ref "R31") (pin "1") (pinfunction "1_1") (pintype "passive"))
    )
    (net (code "95") (name "unconnected-(RT1-Pad1)") (class "Default")
      (node (ref "RT1") (pin "1") (pinfunction "1_1") (pintype "passive"))
    )
    (net (code "96") (name "unconnected-(RT1-Pad2)") (class "Default")
      (node (ref "RT1") (pin "2") (pinfunction "2_2") (pintype "passive"))
    )
    (net (code "97") (name "unconnected-(RT2-Pad1)") (class "Default")
      (node (ref "RT2") (pin "1") (pinfunction "1_1") (pintype "passive"))
    )
    (net (code "98") (name "unconnected-(RT2-Pad2)") (class "Default")
      (node (ref "RT2") (pin "2") (pinfunction "2_2") (pintype "passive"))
    )
  )
)
